# P09_Power.net
KiCad netlist of a schematic drawn in Altium Designer
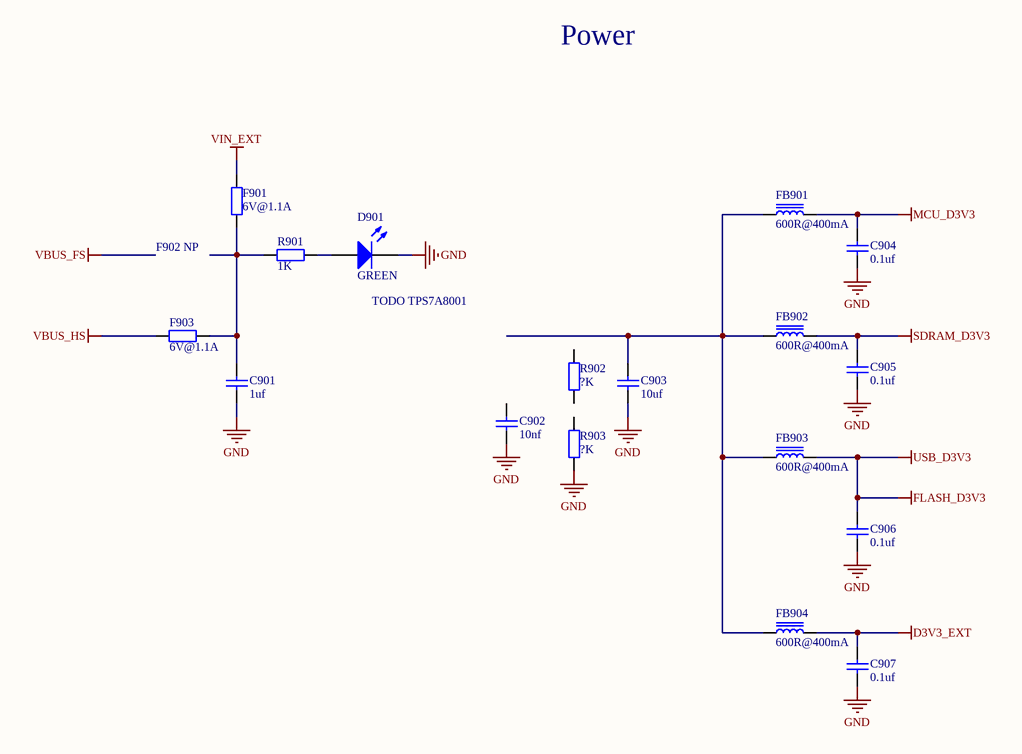
[diagram p0: P09.Power.SchDoc]

(export (version "E")
  (design (tool "Eeschema 10.0.6"))
  (components
    (comp (ref "C901")
      (value "1uf")
      (footprint "C0603")
      (fields (field (name "Comment") "Cap"))
      (libsource (lib "carrot_lib") (part "Cap"))
    )
    (comp (ref "C902")
      (value "10nf")
      (footprint "C0603")
      (fields (field (name "Comment") "Cap"))
      (libsource (lib "carrot_lib") (part "Cap"))
    )
    (comp (ref "C903")
      (value "10uf")
      (footprint "C0805")
      (fields (field (name "Comment") "Cap"))
      (libsource (lib "carrot_lib") (part "Cap"))
    )
    (comp (ref "C904")
      (value "0.1uf")
      (footprint "C0603")
      (fields (field (name "Comment") "Cap"))
      (libsource (lib "carrot_lib") (part "Cap"))
    )
    (comp (ref "C905")
      (value "0.1uf")
      (footprint "C0603")
      (fields (field (name "Comment") "Cap"))
      (libsource (lib "carrot_lib") (part "Cap"))
    )
    (comp (ref "C906")
      (value "0.1uf")
      (footprint "C0603")
      (fields (field (name "Comment") "Cap"))
      (libsource (lib "carrot_lib") (part "Cap"))
    )
    (comp (ref "C907")
      (value "0.1uf")
      (footprint "C0603")
      (fields (field (name "Comment") "Cap"))
      (libsource (lib "carrot_lib") (part "Cap"))
    )
    (comp (ref "D901")
      (value "GREEN")
      (footprint "LED0603")
      (fields (field (name "Comment") "LED"))
      (libsource (lib "carrot_lib") (part "LED"))
    )
    (comp (ref "F901")
      (value "6V@1.1A")
      (footprint "F0805")
      (fields (field (name "Comment") "Fuse"))
      (libsource (lib "carrot_lib") (part "Fuse"))
    )
    (comp (ref "F903")
      (value "6V@1.1A")
      (footprint "F0805")
      (fields (field (name "Comment") "Fuse"))
      (libsource (lib "") (part "Fuse_1"))
    )
    (comp (ref "FB901")
      (value "600R@400mA")
      (footprint "FB0603")
      (description "Ferrite Bead")
      (libsource (lib "carrot_lib") (part "Ferrite Bead"))
    )
    (comp (ref "FB902")
      (value "600R@400mA")
      (footprint "FB0603")
      (description "Ferrite Bead")
      (libsource (lib "carrot_lib") (part "Ferrite Bead"))
    )
    (comp (ref "FB903")
      (value "600R@400mA")
      (footprint "FB0603")
      (description "Ferrite Bead")
      (libsource (lib "carrot_lib") (part "Ferrite Bead"))
    )
    (comp (ref "FB904")
      (value "600R@400mA")
      (footprint "FB0603")
      (description "Ferrite Bead")
      (libsource (lib "carrot_lib") (part "Ferrite Bead"))
    )
    (comp (ref "R901")
      (value "1K")
      (footprint "R0603")
      (description "电阻")
      (fields (field (name "Comment") "Res"))
      (libsource (lib "carrot_lib") (part "Res"))
    )
    (comp (ref "R902")
      (value "?K")
      (footprint "R0603")
      (description "电阻")
      (fields (field (name "Comment") "Res"))
      (libsource (lib "") (part "Res_1"))
    )
    (comp (ref "R903")
      (value "?K")
      (footprint "R0603")
      (description "电阻")
      (fields (field (name "Comment") "Res"))
      (libsource (lib "") (part "Res_1"))
    )
  )
  (nets
    (net (code "1") (name "D3V3_EXT") (class "Default")
      (node (ref "C907") (pin "2") (pinfunction "2_2") (pintype "passive"))
      (node (ref "FB904") (pin "2") (pinfunction "2_2") (pintype "passive"))
    )
    (net (code "2") (name "FLASH_D3V3") (class "Default")
      (node (ref "C906") (pin "2") (pinfunction "2_2") (pintype "passive"))
      (node (ref "FB903") (pin "2") (pinfunction "2_2") (pintype "passive"))
    )
    (net (code "3") (name "GND") (class "Default")
      (node (ref "C901") (pin "1") (pinfunction "1_1") (pintype "passive"))
      (node (ref "C902") (pin "1") (pinfunction "1_1") (pintype "passive"))
      (node (ref "C903") (pin "1") (pinfunction "1_1") (pintype "passive"))
      (node (ref "C904") (pin "1") (pinfunction "1_1") (pintype "passive"))
      (node (ref "C905") (pin "1") (pinfunction "1_1") (pintype "passive"))
      (node (ref "C906") (pin "1") (pinfunction "1_1") (pintype "passive"))
      (node (ref "C907") (pin "1") (pinfunction "1_1") (pintype "passive"))
      (node (ref "D901") (pin "2") (pinfunction "K_2") (pintype "passive"))
      (node (ref "R903") (pin "1") (pinfunction "1_1") (pintype "passive"))
    )
    (net (code "4") (name "MCU_D3V3") (class "Default")
      (node (ref "C904") (pin "2") (pinfunction "2_2") (pintype "passive"))
      (node (ref "FB901") (pin "2") (pinfunction "2_2") (pintype "passive"))
    )
    (net (code "5") (name "Net-(C901-Pad2)") (class "Default")
      (node (ref "C901") (pin "2") (pinfunction "2_2") (pintype "passive"))
      (node (ref "F901") (pin "1") (pinfunction "1_1") (pintype "passive"))
      (node (ref "F903") (pin "2") (pinfunction "2_2") (pintype "passive"))
      (node (ref "R901") (pin "1") (pinfunction "1_1") (pintype "passive"))
    )
    (net (code "6") (name "Net-(C903-Pad2)") (class "Default")
      (node (ref "C903") (pin "2") (pinfunction "2_2") (pintype "passive"))
      (node (ref "FB901") (pin "1") (pinfunction "1_1") (pintype "passive"))
      (node (ref "FB902") (pin "1") (pinfunction "1_1") (pintype "passive"))
      (node (ref "FB903") (pin "1") (pinfunction "1_1") (pintype "passive"))
      (node (ref "FB904") (pin "1") (pinfunction "1_1") (pintype "passive"))
    )
    (net (code "7") (name "Net-(D901-A)") (class "Default")
      (node (ref "D901") (pin "1") (pinfunction "A_1") (pintype "passive"))
      (node (ref "R901") (pin "2") (pinfunction "2_2") (pintype "passive"))
    )
    (net (code "8") (name "SDRAM_D3V3") (class "Default")
      (node (ref "C905") (pin "2") (pinfunction "2_2") (pintype "passive"))
      (node (ref "FB902") (pin "2") (pinfunction "2_2") (pintype "passive"))
    )
    (net (code "10") (name "VBUS_HS") (class "Default")
      (node (ref "F903") (pin "1") (pinfunction "1_1") (pintype "passive"))
    )
    (net (code "11") (name "VIN_EXT") (class "Default")
      (node (ref "F901") (pin "2") (pinfunction "2_2") (pintype "passive"))
    )
    (net (code "12") (name "unconnected-(C902-Pad2)") (class "Default")
      (node (ref "C902") (pin "2") (pinfunction "2_2") (pintype "passive"))
    )
    (net (code "13") (name "unconnected-(R902-Pad1)") (class "Default")
      (node (ref "R902") (pin "1") (pinfunction "1_1") (pintype "passive"))
    )
    (net (code "14") (name "unconnected-(R902-Pad2)") (class "Default")
      (node (ref "R902") (pin "2") (pinfunction "2_2") (pintype "passive"))
    )
    (net (code "15") (name "unconnected-(R903-Pad2)") (class "Default")
      (node (ref "R903") (pin "2") (pinfunction "2_2") (pintype "passive"))
    )
  )
)
